# design.net
KiCad netlist of a schematic drawn in Altium Designer
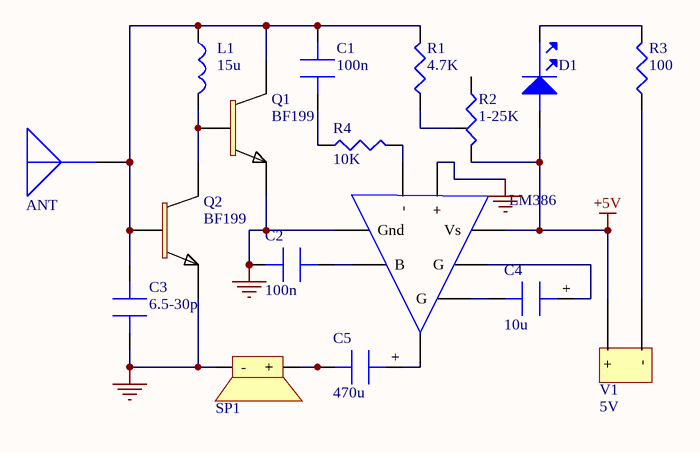
[diagram p0: Курсовая.SchDoc]

(export (version "E")
  (design (tool "Eeschema 10.0.6"))
  (components
    (comp (ref "ANT") (value "ANT") (footprint "Курсовая:ANT") (libsource (lib "Курсовая") (part "ANT")))
    (comp (ref "C1")
      (value "100n")
      (footprint "Курсовая:100n capacitor")
      (description "Cap Ceramic 0.1uF 10V X5R 10% SMD 0402 85C Paper T/R")
      (fields
        (field (name "MANUFACTURER") "Samsung")
        (field (name "MANUFACTURER PART NUMBER") "CL05A104KP5NNND")
      )
      (libsource (lib "Курсовая") (part "CL05A104KP5NNND_1"))
    )
    (comp (ref "C2")
      (value "100n")
      (footprint "Курсовая:100n capacitor")
      (description "Cap Ceramic 0.1uF 10V X5R 10% SMD 0402 85C Paper T/R")
      (fields
        (field (name "MANUFACTURER") "Samsung")
        (field (name "MANUFACTURER PART NUMBER") "CL05A104KP5NNND")
      )
      (libsource (lib "Курсовая") (part "CL05A104KP5NNND"))
    )
    (comp (ref "C3")
      (value "6.5-30p")
      (footprint "Курсовая:6-30pF capacitor")
      (description "Cap Trimmer SMD")
      (fields
        (field (name "MANUFACTURER") "Sprague Goodman")
        (field (name "MANUFACTURER PART NUMBER") "GKG30086-05")
      )
      (libsource (lib "Курсовая") (part "GKG30086-05"))
    )
    (comp (ref "C4")
      (value "10u")
      (footprint "Курсовая:10uF capacitor")
      (description "Aluminum Electrolytic Capacitors - Radial Leaded 10uF 63 Volts 20% LYTICS/IC")
      (fields
        (field (name "MANUFACTURER") "CDE Illinois Capacitor")
        (field (name "MANUFACTURER PART NUMBER") "106CKE063M")
      )
      (libsource (lib "Курсовая") (part "106CKE063M"))
    )
    (comp (ref "C5")
      (value "470u")
      (footprint "Курсовая:Capacitor 470u")
      (description "Cap Aluminum 470uF 6.3V 20% (6.3 X 11.2mm) Radial 5mm 230mA 1000 hr 105C Ammo Pack")
      (fields
        (field (name "MANUFACTURER") "Panasonic")
        (field (name "MANUFACTURER PART NUMBER") "ECA-0JHG471B")
      )
      (libsource (lib "Курсовая") (part "ECA-0JHG471B"))
    )
    (comp (ref "D1")
      (value "LTW-M140ZVS")
      (footprint "Курсовая:LED")
      (description "White 120° Viewing Angle 3 x 1.05 x 1.2 mm 3.5 V 20 mA Surface Mount Lamp")
      (fields (field (name "MANUFACTURER") "Vishay Lite-On"))
      (libsource (lib "Курсовая") (part "LTW-M140ZVS"))
    )
    (comp (ref "L1")
      (value "15u")
      (footprint "Курсовая:15uH inductor")
      (description "BOURNS JW MILLER   78F150J-RC   CHOKE, 15UH, 150MA, 5%, 16MHZ")
      (fields
        (field (name "MANUFACTURER") "Bourns JW Miller")
        (field (name "MANUFACTURER PART NUMBER") "78F150J-RC")
      )
      (libsource (lib "Курсовая") (part "78F150J-RC"))
    )
    (comp (ref "LM386")
      (value "LM386N-3")
      (footprint "Курсовая:LM386")
      (description "Audio Amp Speaker 1-CH Mono 0.7W Class-AB 8-Pin PDIP Rail")
      (fields (field (name "MANUFACTURER") "TI National Semiconductor"))
      (libsource (lib "Курсовая") (part "LM386N-3"))
    )
    (comp (ref "Q1")
      (value "BF199")
      (footprint "Курсовая:BF199")
      (description "TRANSISTOR RF NPN 25V 50MA TO-92")
      (fields (field (name "MANUFACTURER") "ON Semiconductor / Fairchild"))
      (libsource (lib "Курсовая") (part "BF199"))
    )
    (comp (ref "Q2")
      (value "BF199")
      (footprint "Курсовая:BF199")
      (description "TRANSISTOR RF NPN 25V 50MA TO-92")
      (fields (field (name "MANUFACTURER") "ON Semiconductor / Fairchild"))
      (libsource (lib "Курсовая") (part "BF199"))
    )
    (comp (ref "R1")
      (value "4.7K")
      (footprint "Курсовая:4.7K resistor")
      (description "Thick Film Resistors - SMD 0.1W 4.7Kohm 20% 200ppm")
      (fields
        (field (name "MANUFACTURER") "KOA Speer")
        (field (name "MANUFACTURER PART NUMBER") "SG731JTTD472M")
      )
      (libsource (lib "Курсовая") (part "SG731JTTD472M"))
    )
    (comp (ref "R2")
      (value "1-25K")
      (footprint "Курсовая:Potentiometer")
      (description "Res Carbon Film Trimmer 25K Ohm 20% 0.15W 1(Elec)/1(Mech)Turn (9.8 X 5 X 12.1mm) Pin Thru-Hole")
      (fields
        (field (name "MANUFACTURER") "TE Connectivity Citec")
        (field (name "MANUFACTURER PART NUMBER") "CB6MH253M")
      )
      (libsource (lib "Курсовая") (part "CB6MH253M"))
    )
    (comp (ref "R3")
      (value "100")
      (footprint "Курсовая:100Ohm resistor")
      (description "Res 100 Ohm 20% 1/4W 0805")
      (fields
        (field (name "MANUFACTURER") "Yageo")
        (field (name "MANUFACTURER PART NUMBER") "SR0805MR-7W100RL")
      )
      (libsource (lib "Курсовая") (part "SR0805MR-7W100RL"))
    )
    (comp (ref "R4")
      (value "10K")
      (footprint "Курсовая:10K resistor")
      (description "Res Thick Film 0603 10kOhm 20% 1/10W ±200ppm/°C Molded Paper T/R")
      (fields
        (field (name "MANUFACTURER") "Stackpole Electronics")
        (field (name "MANUFACTURER PART NUMBER") "FCR0603MT10K0")
      )
      (libsource (lib "Курсовая") (part "FCR0603MT10K0"))
    )
    (comp (ref "SP1")
      (value "WSP-7704")
      (footprint "Курсовая:Dynamic")
      (fields (field (name "MANUFACTURER") "Soberton"))
      (libsource (lib "Курсовая") (part "WSP-7704"))
    )
    (comp (ref "V1")
      (value "5V")
      (footprint "Курсовая:mini-USb port")
      (description "USB Connectors MINI USB SINGLE SMT 5P HORIZONTAL")
      (fields (field (name "MANUFACTURER") "Harwin") (field (name "MANUFACTURER PART NUMBER") "M701-340542"))
      (libsource (lib "Курсовая") (part "M701-340542"))
    )
  )
  (nets
    (net (code "1") (name "+5V") (class "Default")
      (node (ref "D1") (pin "2") (pinfunction "2_2") (pintype "passive"))
      (node (ref "LM386") (pin "6") (pinfunction "Vs_6") (pintype "passive"))
      (node (ref "R2") (pin "2") (pinfunction "2_2") (pintype "passive"))
      (node (ref "V1") (pin "2") (pinfunction "+_2") (pintype "passive"))
    )
    (net (code "2") (name "GND") (class "Default")
      (node (ref "C2") (pin "1") (pinfunction "1_1") (pintype "passive"))
      (node (ref "C3") (pin "1") (pinfunction "1_1") (pintype "passive"))
      (node (ref "LM386") (pin "3") (pinfunction "+_3") (pintype "passive"))
      (node (ref "LM386") (pin "4") (pinfunction "Gnd_4") (pintype "passive"))
      (node (ref "Q1") (pin "3") (pinfunction "Е_3") (pintype "passive"))
      (node (ref "Q2") (pin "3") (pinfunction "Е_3") (pintype "passive"))
      (node (ref "SP1") (pin "2") (pinfunction "-_2") (pintype "passive"))
    )
    (net (code "3") (name "Net-(C1-Pad1)") (class "Default")
      (node (ref "C1") (pin "1") (pinfunction "1_1") (pintype "passive"))
      (node (ref "R4") (pin "1") (pinfunction "1_1") (pintype "passive"))
    )
    (net (code "4") (name "Net-(C4-1)") (class "Default")
      (node (ref "C4") (pin "+") (pinfunction "1_+") (pintype "passive"))
      (node (ref "LM386") (pin "1") (pinfunction "G_1") (pintype "passive"))
    )
    (net (code "5") (name "Net-(C4-Pad3)") (class "Default")
      (node (ref "C4") (pin "3") (pinfunction "3_3") (pintype "passive"))
      (node (ref "LM386") (pin "8") (pinfunction "G_8") (pintype "passive"))
    )
    (net (code "6") (name "Net-(C5-1)") (class "Default")
      (node (ref "C5") (pin "+") (pinfunction "1_+") (pintype "passive"))
      (node (ref "LM386") (pin "5") (pinfunction "5_5") (pintype "passive"))
    )
    (net (code "7") (name "Net-(D1-Pad1)") (class "Default")
      (node (ref "D1") (pin "1") (pinfunction "1_1") (pintype "passive"))
      (node (ref "R3") (pin "2") (pinfunction "2_2") (pintype "passive"))
    )
    (net (code "8") (name "Net-(LM386--)") (class "Default")
      (node (ref "LM386") (pin "2") (pinfunction "-_2") (pintype "passive"))
      (node (ref "R4") (pin "2") (pinfunction "2_2") (pintype "passive"))
    )
    (net (code "9") (name "Net-(LM386-B)") (class "Default")
      (node (ref "C2") (pin "2") (pinfunction "2_2") (pintype "passive"))
      (node (ref "LM386") (pin "7") (pinfunction "B_7") (pintype "passive"))
    )
    (net (code "10") (name "Net-(Q1-В)") (class "Default")
      (node (ref "L1") (pin "7") (pinfunction "7_7") (pintype "passive"))
      (node (ref "Q1") (pin "2") (pinfunction "В_2") (pintype "passive"))
      (node (ref "Q2") (pin "1") (pinfunction "С_1") (pintype "passive"))
    )
    (net (code "11") (name "Net-(Q1-С)") (class "Default")
      (node (ref "ANT") (pin "1") (pinfunction "1_1") (pintype "passive"))
      (node (ref "C1") (pin "2") (pinfunction "2_2") (pintype "passive"))
      (node (ref "C3") (pin "2") (pinfunction "2_2") (pintype "passive"))
      (node (ref "L1") (pin "6") (pinfunction "6_6") (pintype "passive"))
      (node (ref "Q1") (pin "1") (pinfunction "С_1") (pintype "passive"))
      (node (ref "Q2") (pin "2") (pinfunction "В_2") (pintype "passive"))
      (node (ref "R1") (pin "2") (pinfunction "2_2") (pintype "passive"))
    )
    (net (code "12") (name "Net-(R1-Pad1)") (class "Default")
      (node (ref "R1") (pin "1") (pinfunction "1_1") (pintype "passive"))
      (node (ref "R2") (pin "3") (pinfunction "3_3") (pintype "passive"))
    )
    (net (code "13") (name "Net-(SP1-+)") (class "Default")
      (node (ref "C5") (pin "2") (pinfunction "2_2") (pintype "passive"))
      (node (ref "C5") (pin "3") (pinfunction "3_3") (pintype "passive"))
      (node (ref "SP1") (pin "1") (pinfunction "+_1") (pintype "passive"))
    )
    (net (code "14") (name "Net-(V1--)") (class "Default")
      (node (ref "R3") (pin "1") (pinfunction "1_1") (pintype "passive"))
      (node (ref "V1") (pin "1") (pinfunction "-_1") (pintype "passive"))
    )
    (net (code "15") (name "unconnected-(R2-Pad1)") (class "Default")
      (node (ref "R2") (pin "1") (pinfunction "1_1") (pintype "passive"))
    )
  )
)
